# ethernet.net
KiCad netlist of a schematic drawn in Altium Designer
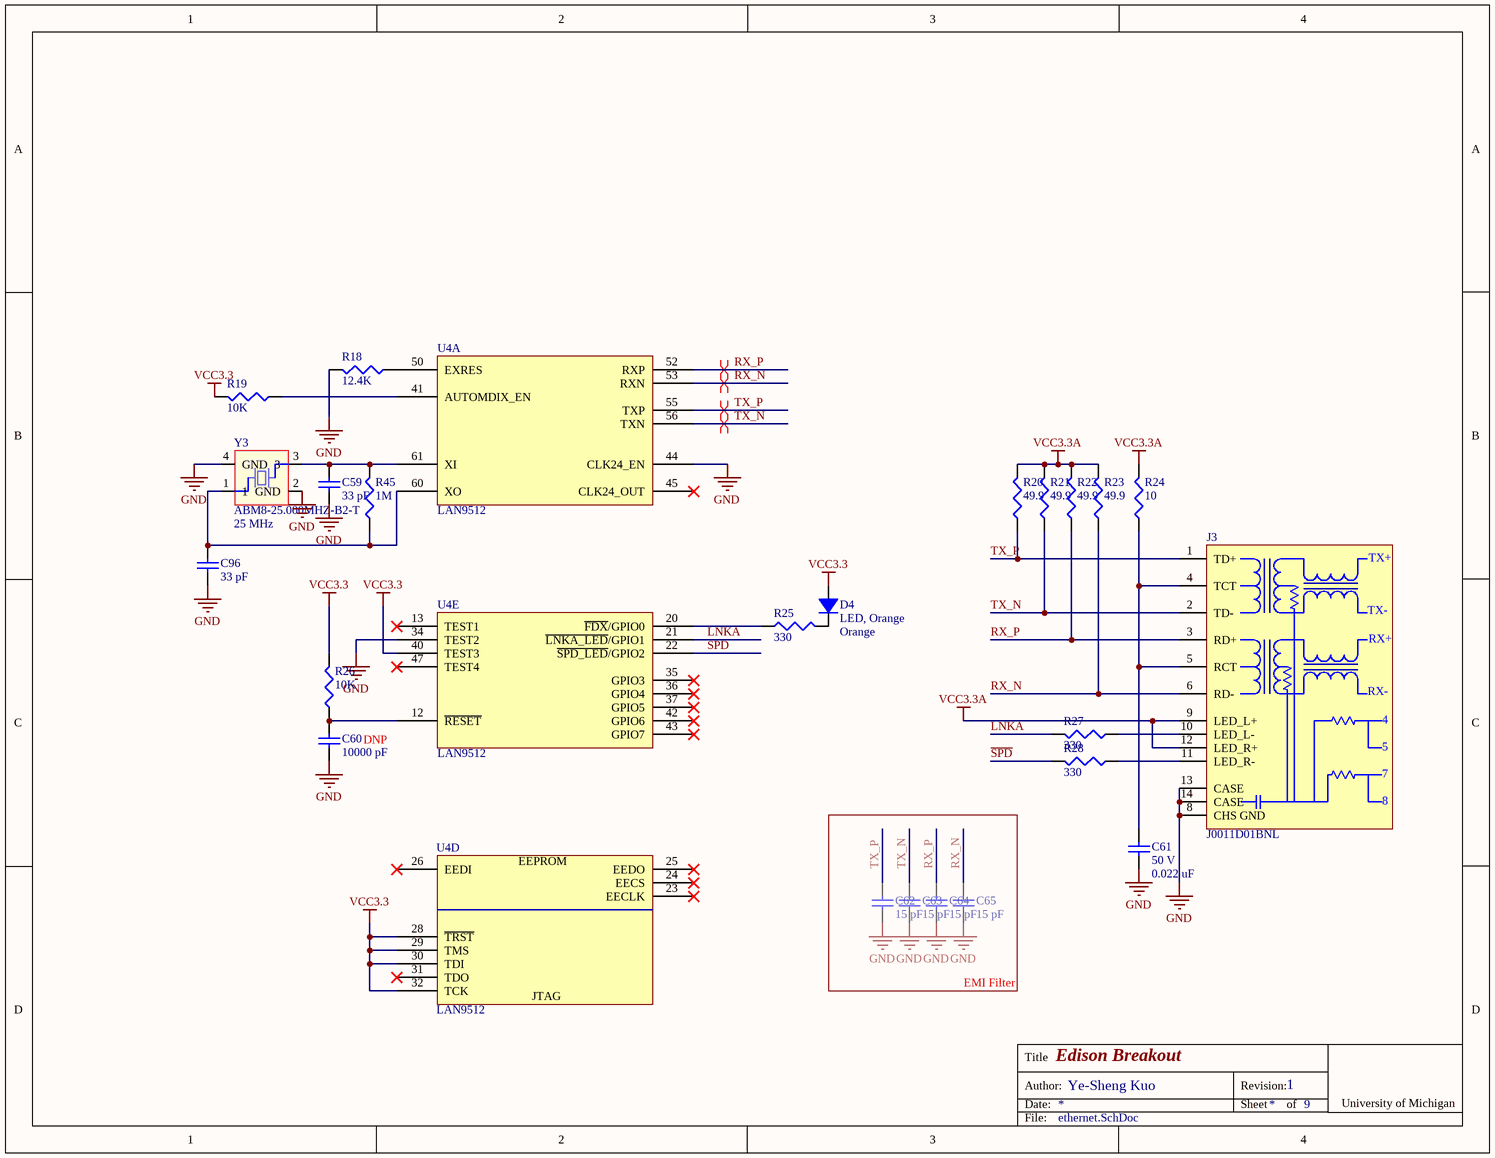
[diagram p0: ethernet.SchDoc]

(export (version "E")
  (design (tool "Eeschema 10.0.6"))
  (components
    (comp (ref "C59")
      (value "33 pF")
      (footprint "0402")
      (description "Ceramic capacitor, 33 pF, 0402 package")
      (fields (field (name "TOLERANCE") "5%") (field (name "Comment") "Ceramic capacitor"))
      (libsource (lib "rlc") (part "C_33p_0402_ceramic"))
    )
    (comp (ref "C60")
      (value "10000 pF")
      (footprint "0402")
      (description "Ceramic capacitor, 10000 pF, 16 V, 0402 package")
      (fields (field (name "TOLERANCE") "10%") (field (name "Comment") "Ceramic capacitor"))
      (libsource (lib "rlc") (part "C_10000p_16V_0402_ceramic"))
    )
    (comp (ref "C61")
      (value "0.022 uF")
      (footprint "0402")
      (description "Ceramic capacitor, 0.022 uF, 0402 package")
      (fields
        (field (name "TOLERANCE") "10%")
        (field (name "VOLTAGE RATED") "50 V")
        (field (name "Comment") "Ceramic capacitor")
      )
      (libsource (lib "rlc") (part "C_0.022u_50V_0402_ceramic"))
    )
    (comp (ref "C62")
      (value "15 pF")
      (footprint "0402")
      (description "Ceramic capacitor, 15 pF, 25V, 0402 package")
      (fields (field (name "TOLERANCE") "5%") (field (name "Comment") "Ceramic capacitor"))
      (libsource (lib "rlc") (part "C_15p_25V_0402_ceramic"))
    )
    (comp (ref "C63")
      (value "15 pF")
      (footprint "0402")
      (description "Ceramic capacitor, 15 pF, 25V, 0402 package")
      (fields (field (name "TOLERANCE") "5%") (field (name "Comment") "Ceramic capacitor"))
      (libsource (lib "rlc") (part "C_15p_25V_0402_ceramic"))
    )
    (comp (ref "C64")
      (value "15 pF")
      (footprint "0402")
      (description "Ceramic capacitor, 15 pF, 25V, 0402 package")
      (fields (field (name "TOLERANCE") "5%") (field (name "Comment") "Ceramic capacitor"))
      (libsource (lib "rlc") (part "C_15p_25V_0402_ceramic"))
    )
    (comp (ref "C65")
      (value "15 pF")
      (footprint "0402")
      (description "Ceramic capacitor, 15 pF, 25V, 0402 package")
      (fields (field (name "TOLERANCE") "5%") (field (name "Comment") "Ceramic capacitor"))
      (libsource (lib "rlc") (part "C_15p_25V_0402_ceramic"))
    )
    (comp (ref "C96")
      (value "33 pF")
      (footprint "0402")
      (description "Ceramic capacitor, 33 pF, 0402 package")
      (fields (field (name "TOLERANCE") "5%") (field (name "Comment") "Ceramic capacitor"))
      (libsource (lib "rlc") (part "C_33p_0402_ceramic"))
    )
    (comp (ref "D4")
      (value "LED, Orange")
      (footprint "0402 - DIODE")
      (description "LED, Orange, 0402")
      (fields (field (name "COLOR") "Orange"))
      (libsource (lib "rlc") (part "D_LED_ORANGE_0402"))
    )
    (comp (ref "J3")
      (value "J0011D01BNL")
      (footprint "J0011D01BNL")
      (description "1x1 Tab-Down RJ45")
      (libsource (lib "connectors") (part "J0011D01BNL"))
    )
    (comp (ref "R18")
      (value "12.4K")
      (footprint "0402")
      (description "Chip resistor, 12.4K, 0402 package")
      (fields (field (name "TOLERANCE") "1%") (field (name "POWER") "1/16 W"))
      (libsource (lib "rlc") (part "R_12.4K_0402"))
    )
    (comp (ref "R19")
      (value "10K")
      (footprint "0402")
      (description "Chip resistor, 10K, 0402 package")
      (fields (field (name "TOLERANCE") "1%") (field (name "POWER") "1/16 W"))
      (libsource (lib "rlc") (part "R_10K_0402"))
    )
    (comp (ref "R20")
      (value "49.9")
      (footprint "0402")
      (description "Chip resistor, 49.9, 0402 package")
      (fields (field (name "TOLERANCE") "1%") (field (name "POWER") "1/16 W"))
      (libsource (lib "rlc") (part "R_49.9_0402"))
    )
    (comp (ref "R21")
      (value "49.9")
      (footprint "0402")
      (description "Chip resistor, 49.9, 0402 package")
      (fields (field (name "TOLERANCE") "1%") (field (name "POWER") "1/16 W"))
      (libsource (lib "rlc") (part "R_49.9_0402"))
    )
    (comp (ref "R22")
      (value "49.9")
      (footprint "0402")
      (description "Chip resistor, 49.9, 0402 package")
      (fields (field (name "TOLERANCE") "1%") (field (name "POWER") "1/16 W"))
      (libsource (lib "rlc") (part "R_49.9_0402"))
    )
    (comp (ref "R23")
      (value "49.9")
      (footprint "0402")
      (description "Chip resistor, 49.9, 0402 package")
      (fields (field (name "TOLERANCE") "1%") (field (name "POWER") "1/16 W"))
      (libsource (lib "rlc") (part "R_49.9_0402"))
    )
    (comp (ref "R24")
      (value "10")
      (footprint "0402")
      (description "Chip resistor, 10, 0402 package")
      (fields (field (name "TOLERANCE") "1%") (field (name "POWER") "1/16 W"))
      (libsource (lib "rlc") (part "R_10_0402"))
    )
    (comp (ref "R25")
      (value "330")
      (footprint "0402")
      (description "Chip resistor, 330, 0402 package")
      (fields (field (name "TOLERANCE") "1%") (field (name "POWER") "1/16 W"))
      (libsource (lib "rlc") (part "R_330_0402"))
    )
    (comp (ref "R26")
      (value "10K")
      (footprint "0402")
      (description "Chip resistor, 10K, 0402 package")
      (fields (field (name "TOLERANCE") "1%") (field (name "POWER") "1/16 W"))
      (libsource (lib "rlc") (part "R_10K_0402"))
    )
    (comp (ref "R27")
      (value "330")
      (footprint "0402")
      (description "Chip resistor, 330, 0402 package")
      (fields (field (name "TOLERANCE") "1%") (field (name "POWER") "1/16 W"))
      (libsource (lib "rlc") (part "R_330_0402"))
    )
    (comp (ref "R28")
      (value "330")
      (footprint "0402")
      (description "Chip resistor, 330, 0402 package")
      (fields (field (name "TOLERANCE") "1%") (field (name "POWER") "1/16 W"))
      (libsource (lib "rlc") (part "R_330_0402"))
    )
    (comp (ref "R45")
      (value "1M")
      (footprint "0402")
      (description "Chip resistor, 1M, 0402 package")
      (fields (field (name "TOLERANCE") "1%") (field (name "POWER") "1/16 W"))
      (libsource (lib "rlc") (part "R_1M_0402"))
    )
    (comp (ref "U4")
      (value "LAN9512")
      (footprint "QFN-64")
      (description "USB 2.0 Hub and 10/100  Ethernet Controller")
      (libsource (lib "ethernet") (part "LAN9512"))
    )
    (comp (ref "Y3")
      (value "ABM8-25.000MHZ-B2-T")
      (footprint "ABM8")
      (description "Crystal 25.0000MHz 20ppm 18pF 50 Ohm")
      (fields (field (name "FREQUENCY") "25 MHz"))
      (libsource (lib "crystal_oscillators_rtc") (part "ABM8-25.000MHZ-B2-T"))
    )
  )
  (nets
    (net (code "1") (name "/RX_N") (class "Default")
      (node (ref "C65") (pin "1") (pintype "passive"))
      (node (ref "J3") (pin "6") (pinfunction "RD-_6") (pintype "passive"))
      (node (ref "R23") (pin "2") (pintype "passive"))
      (node (ref "U4") (pin "53") (pinfunction "RXN_53") (pintype "passive"))
    )
    (net (code "2") (name "/RX_P") (class "Default")
      (node (ref "C64") (pin "1") (pintype "passive"))
      (node (ref "J3") (pin "3") (pinfunction "RD+_3") (pintype "passive"))
      (node (ref "R22") (pin "2") (pintype "passive"))
      (node (ref "U4") (pin "52") (pinfunction "RXP_52") (pintype "passive"))
    )
    (net (code "3") (name "/TX_N") (class "Default")
      (node (ref "C63") (pin "1") (pintype "passive"))
      (node (ref "J3") (pin "2") (pinfunction "TD-_2") (pintype "passive"))
      (node (ref "R21") (pin "2") (pintype "passive"))
      (node (ref "U4") (pin "56") (pinfunction "TXN_56") (pintype "passive"))
    )
    (net (code "4") (name "/TX_P") (class "Default")
      (node (ref "C62") (pin "1") (pintype "passive"))
      (node (ref "J3") (pin "1") (pinfunction "TD+_1") (pintype "passive"))
      (node (ref "R20") (pin "2") (pintype "passive"))
      (node (ref "U4") (pin "55") (pinfunction "TXP_55") (pintype "passive"))
    )
    (net (code "5") (name "/~{LNKA}") (class "Default")
      (node (ref "R27") (pin "1") (pintype "passive"))
      (node (ref "U4") (pin "21") (pinfunction "~{LNKA_LED}/GPIO1_21") (pintype "passive"))
    )
    (net (code "6") (name "/~{SPD}") (class "Default")
      (node (ref "R28") (pin "1") (pintype "passive"))
      (node (ref "U4") (pin "22") (pinfunction "~{SPD_LED}/GPIO2_22") (pintype "passive"))
    )
    (net (code "7") (name "GND") (class "Default")
      (node (ref "C59") (pin "2") (pintype "passive"))
      (node (ref "C60") (pin "2") (pintype "passive"))
      (node (ref "C61") (pin "2") (pintype "passive"))
      (node (ref "C62") (pin "2") (pintype "passive"))
      (node (ref "C63") (pin "2") (pintype "passive"))
      (node (ref "C64") (pin "2") (pintype "passive"))
      (node (ref "C65") (pin "2") (pintype "passive"))
      (node (ref "C96") (pin "2") (pintype "passive"))
      (node (ref "J3") (pin "13") (pinfunction "CASE_13") (pintype "passive"))
      (node (ref "J3") (pin "14") (pinfunction "CASE_14") (pintype "passive"))
      (node (ref "J3") (pin "8") (pinfunction "CHS_GND_8") (pintype "passive"))
      (node (ref "R18") (pin "1") (pintype "passive"))
      (node (ref "U4") (pin "34") (pinfunction "TEST2_34") (pintype "passive"))
      (node (ref "U4") (pin "44") (pinfunction "CLK24_EN_44") (pintype "passive"))
      (node (ref "Y3") (pin "2") (pinfunction "GND_2") (pintype "passive"))
      (node (ref "Y3") (pin "4") (pinfunction "GND_4") (pintype "passive"))
    )
    (net (code "8") (name "Net-(D4-Pad2)") (class "Default")
      (node (ref "D4") (pin "2") (pintype "passive"))
      (node (ref "R25") (pin "1") (pintype "passive"))
    )
    (net (code "9") (name "Net-(J3-LED_L-)") (class "Default")
      (node (ref "J3") (pin "10") (pinfunction "LED_L-_10") (pintype "passive"))
      (node (ref "R27") (pin "2") (pintype "passive"))
    )
    (net (code "10") (name "Net-(J3-LED_R-)") (class "Default")
      (node (ref "J3") (pin "11") (pinfunction "LED_R-_11") (pintype "passive"))
      (node (ref "R28") (pin "2") (pintype "passive"))
    )
    (net (code "11") (name "Net-(J3-RCT)") (class "Default")
      (node (ref "C61") (pin "1") (pintype "passive"))
      (node (ref "J3") (pin "4") (pinfunction "TCT_4") (pintype "passive"))
      (node (ref "J3") (pin "5") (pinfunction "RCT_5") (pintype "passive"))
      (node (ref "R24") (pin "2") (pintype "passive"))
    )
    (net (code "12") (name "Net-(U4A-AUTOMDIX_EN)") (class "Default")
      (node (ref "R19") (pin "2") (pintype "passive"))
      (node (ref "U4") (pin "41") (pinfunction "AUTOMDIX_EN_41") (pintype "passive"))
    )
    (net (code "13") (name "Net-(U4A-EXRES)") (class "Default")
      (node (ref "R18") (pin "2") (pintype "passive"))
      (node (ref "U4") (pin "50") (pinfunction "EXRES_50") (pintype "passive"))
    )
    (net (code "14") (name "Net-(U4A-XI)") (class "Default")
      (node (ref "C59") (pin "1") (pintype "passive"))
      (node (ref "R45") (pin "1") (pintype "passive"))
      (node (ref "U4") (pin "61") (pinfunction "XI_61") (pintype "passive"))
      (node (ref "Y3") (pin "3") (pinfunction "3_3") (pintype "passive"))
    )
    (net (code "15") (name "Net-(U4A-XO)") (class "Default")
      (node (ref "C96") (pin "1") (pintype "passive"))
      (node (ref "R45") (pin "2") (pintype "passive"))
      (node (ref "U4") (pin "60") (pinfunction "XO_60") (pintype "passive"))
      (node (ref "Y3") (pin "1") (pinfunction "1_1") (pintype "passive"))
    )
    (net (code "16") (name "Net-(U4E-~{FDX}{slash}GPIO0)") (class "Default")
      (node (ref "R25") (pin "2") (pintype "passive"))
      (node (ref "U4") (pin "20") (pinfunction "~{FDX}/GPIO0_20") (pintype "passive"))
    )
    (net (code "17") (name "Net-(U4E-~{RESET})") (class "Default")
      (node (ref "C60") (pin "1") (pintype "passive"))
      (node (ref "R26") (pin "2") (pintype "passive"))
      (node (ref "U4") (pin "12") (pinfunction "~{RESET}_12") (pintype "passive"))
    )
    (net (code "18") (name "VCC3.3") (class "Default")
      (node (ref "D4") (pin "1") (pintype "passive"))
      (node (ref "R19") (pin "1") (pintype "passive"))
      (node (ref "R26") (pin "1") (pintype "passive"))
      (node (ref "U4") (pin "28") (pinfunction "~{TRST}_28") (pintype "passive"))
      (node (ref "U4") (pin "29") (pinfunction "TMS_29") (pintype "passive"))
      (node (ref "U4") (pin "30") (pinfunction "TDI_30") (pintype "passive"))
      (node (ref "U4") (pin "32") (pinfunction "TCK_32") (pintype "passive"))
      (node (ref "U4") (pin "40") (pinfunction "TEST3_40") (pintype "passive"))
    )
    (net (code "19") (name "VCC3.3A") (class "Default")
      (node (ref "J3") (pin "12") (pinfunction "LED_R+_12") (pintype "passive"))
      (node (ref "J3") (pin "9") (pinfunction "LED_L+_9") (pintype "passive"))
      (node (ref "R20") (pin "1") (pintype "passive"))
      (node (ref "R21") (pin "1") (pintype "passive"))
      (node (ref "R22") (pin "1") (pintype "passive"))
      (node (ref "R23") (pin "1") (pintype "passive"))
      (node (ref "R24") (pin "1") (pintype "passive"))
    )
    (net (code "20") (name "unconnected-(U4A-CLK24_OUT-Pad45)") (class "Default")
      (node (ref "U4") (pin "45") (pinfunction "CLK24_OUT_45") (pintype "passive+no_connect"))
    )
    (net (code "21") (name "unconnected-(U4D-EECLK-Pad23)") (class "Default")
      (node (ref "U4") (pin "23") (pinfunction "EECLK_23") (pintype "passive+no_connect"))
    )
    (net (code "22") (name "unconnected-(U4D-EECS-Pad24)") (class "Default")
      (node (ref "U4") (pin "24") (pinfunction "EECS_24") (pintype "passive+no_connect"))
    )
    (net (code "23") (name "unconnected-(U4D-EEDI-Pad26)") (class "Default")
      (node (ref "U4") (pin "26") (pinfunction "EEDI_26") (pintype "passive+no_connect"))
    )
    (net (code "24") (name "unconnected-(U4D-EEDO-Pad25)") (class "Default")
      (node (ref "U4") (pin "25") (pinfunction "EEDO_25") (pintype "passive+no_connect"))
    )
    (net (code "25") (name "unconnected-(U4D-TDO-Pad31)") (class "Default")
      (node (ref "U4") (pin "31") (pinfunction "TDO_31") (pintype "passive+no_connect"))
    )
    (net (code "26") (name "unconnected-(U4E-GPIO3-Pad35)") (class "Default")
      (node (ref "U4") (pin "35") (pinfunction "GPIO3_35") (pintype "passive+no_connect"))
    )
    (net (code "27") (name "unconnected-(U4E-GPIO4-Pad36)") (class "Default")
      (node (ref "U4") (pin "36") (pinfunction "GPIO4_36") (pintype "passive+no_connect"))
    )
    (net (code "28") (name "unconnected-(U4E-GPIO5-Pad37)") (class "Default")
      (node (ref "U4") (pin "37") (pinfunction "GPIO5_37") (pintype "passive+no_connect"))
    )
    (net (code "29") (name "unconnected-(U4E-GPIO6-Pad42)") (class "Default")
      (node (ref "U4") (pin "42") (pinfunction "GPIO6_42") (pintype "passive+no_connect"))
    )
    (net (code "30") (name "unconnected-(U4E-GPIO7-Pad43)") (class "Default")
      (node (ref "U4") (pin "43") (pinfunction "GPIO7_43") (pintype "passive+no_connect"))
    )
    (net (code "31") (name "unconnected-(U4E-TEST1-Pad13)") (class "Default")
      (node (ref "U4") (pin "13") (pinfunction "TEST1_13") (pintype "passive+no_connect"))
    )
    (net (code "32") (name "unconnected-(U4E-TEST4-Pad47)") (class "Default")
      (node (ref "U4") (pin "47") (pinfunction "TEST4_47") (pintype "passive+no_connect"))
    )
  )
)
